# pcb.net
KiCad netlist of a schematic drawn in EAGLE
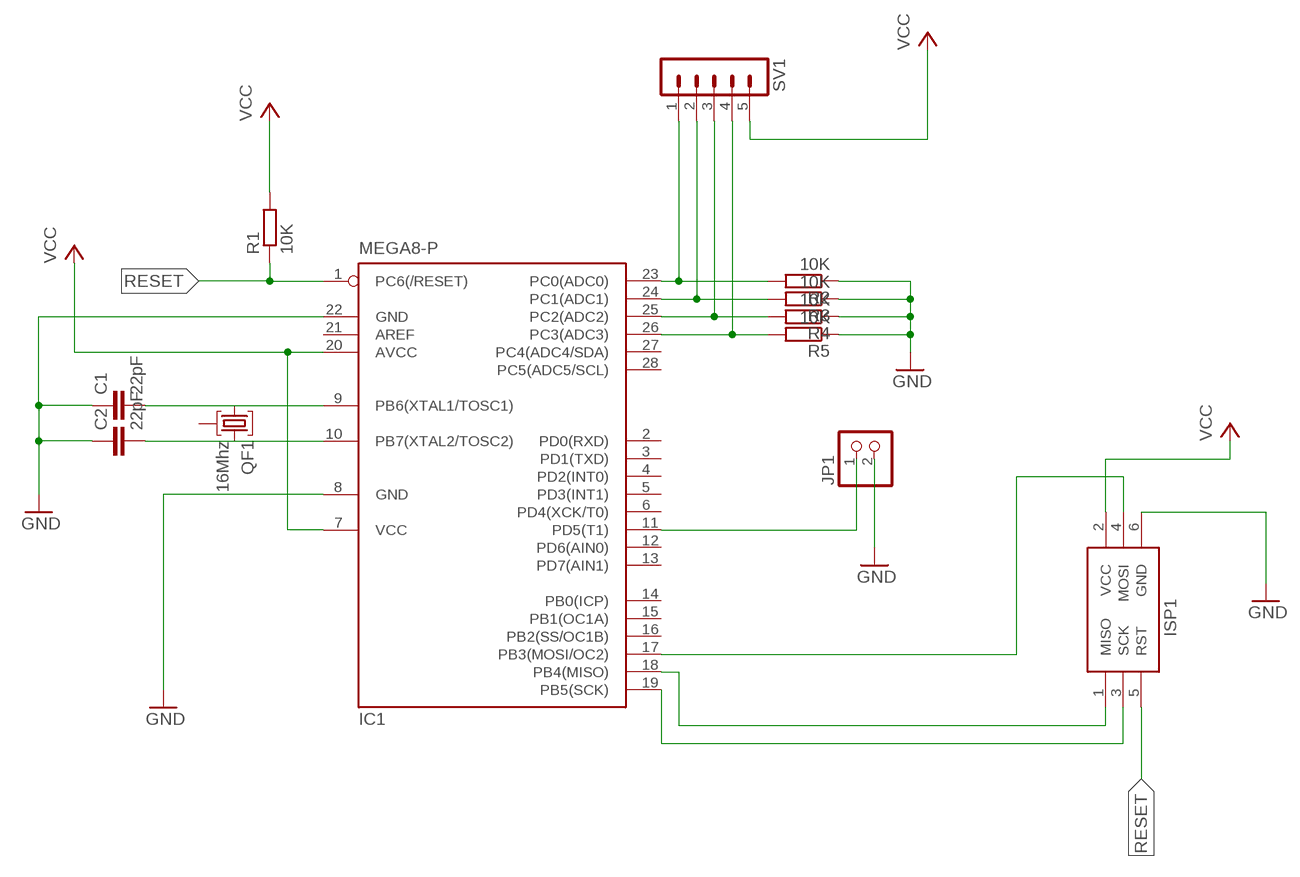
[diagram p0: schematic, sheet 1]

(export (version "E")
  (design (tool "Eeschema 10.0.6"))
  (components
    (comp (ref "C1")
      (value "22pF")
      (footprint "eagle-import:C025-025X050")
      (libsource (lib "eagle-import") (part "C-EU025-025X050"))
    )
    (comp (ref "C2")
      (value "22pF")
      (footprint "eagle-import:C025-025X050")
      (libsource (lib "eagle-import") (part "C-EU025-025X050"))
    )
    (comp (ref "IC1")
      (value "MEGA8-P")
      (footprint "eagle-import:DIL28-3")
      (libsource (lib "eagle-import") (part "MEGA8-P"))
    )
    (comp (ref "ISP1")
      (value "AVRISP-6")
      (footprint "eagle-import:AVRISP")
      (libsource (lib "eagle-import") (part "AVRISP-6"))
    )
    (comp (ref "JP1")
      (value "PINHD-1X2")
      (footprint "eagle-import:1X02")
      (libsource (lib "eagle-import") (part "PINHD-1X2"))
    )
    (comp (ref "QF1")
      (value "16Mhz")
      (footprint "eagle-import:HC49U")
      (libsource (lib "eagle-import") (part "8M10AHC49T"))
    )
    (comp (ref "R1")
      (value "10K")
      (footprint "eagle-import:0204_5")
      (libsource (lib "eagle-import") (part "R-EU_0204/5"))
    )
    (comp (ref "R2")
      (value "10K")
      (footprint "eagle-import:0204_5")
      (libsource (lib "eagle-import") (part "R-EU_0204/5"))
    )
    (comp (ref "R3")
      (value "10K")
      (footprint "eagle-import:0204_5")
      (libsource (lib "eagle-import") (part "R-EU_0204/5"))
    )
    (comp (ref "R4")
      (value "10K")
      (footprint "eagle-import:0204_5")
      (libsource (lib "eagle-import") (part "R-EU_0204/5"))
    )
    (comp (ref "R5")
      (value "10K")
      (footprint "eagle-import:0204_5")
      (libsource (lib "eagle-import") (part "R-EU_0204/5"))
    )
    (comp (ref "SV1")
      (value "MA05-1")
      (footprint "eagle-import:MA05-1")
      (libsource (lib "eagle-import") (part "MA05-1"))
    )
  )
  (nets
    (net (code "1") (name "GND") (class "Default")
      (node (ref "C1") (pin "1") (pinfunction "1_1") (pintype "passive"))
      (node (ref "C2") (pin "1") (pinfunction "1_1") (pintype "passive"))
      (node (ref "IC1") (pin "22") (pinfunction "GND_22") (pintype "power_in"))
      (node (ref "IC1") (pin "8") (pinfunction "GND_8") (pintype "power_in"))
      (node (ref "ISP1") (pin "6") (pinfunction "GND_6") (pintype "power_in"))
      (node (ref "JP1") (pin "2") (pinfunction "2_2") (pintype "passive"))
      (node (ref "R2") (pin "1") (pinfunction "1_1") (pintype "passive"))
      (node (ref "R3") (pin "1") (pinfunction "1_1") (pintype "passive"))
      (node (ref "R4") (pin "1") (pinfunction "1_1") (pintype "passive"))
      (node (ref "R5") (pin "1") (pinfunction "1_1") (pintype "passive"))
    )
    (net (code "2") (name "Net-(IC1-PB3(MOSI{slash}OC2))") (class "Default")
      (node (ref "IC1") (pin "17") (pinfunction "PB3(MOSI/OC2)_17") (pintype "bidirectional"))
      (node (ref "ISP1") (pin "4") (pinfunction "MOSI_4") (pintype "output"))
    )
    (net (code "3") (name "Net-(IC1-PB4(MISO))") (class "Default")
      (node (ref "IC1") (pin "18") (pinfunction "PB4(MISO)_18") (pintype "bidirectional"))
      (node (ref "ISP1") (pin "1") (pinfunction "MISO_1") (pintype "input"))
    )
    (net (code "4") (name "Net-(IC1-PB5(SCK))") (class "Default")
      (node (ref "IC1") (pin "19") (pinfunction "PB5(SCK)_19") (pintype "bidirectional"))
      (node (ref "ISP1") (pin "3") (pinfunction "SCK_3") (pintype "output"))
    )
    (net (code "5") (name "Net-(IC1-PB6(XTAL1{slash}TOSC1))") (class "Default")
      (node (ref "C1") (pin "2") (pinfunction "2_2") (pintype "passive"))
      (node (ref "IC1") (pin "9") (pinfunction "PB6(XTAL1/TOSC1)_9") (pintype "bidirectional"))
      (node (ref "QF1") (pin "1") (pinfunction "1_1") (pintype "passive"))
    )
    (net (code "6") (name "Net-(IC1-PB7(XTAL2{slash}TOSC2))") (class "Default")
      (node (ref "C2") (pin "2") (pinfunction "2_2") (pintype "passive"))
      (node (ref "IC1") (pin "10") (pinfunction "PB7(XTAL2/TOSC2)_10") (pintype "bidirectional"))
      (node (ref "QF1") (pin "3") (pinfunction "3_3") (pintype "passive"))
    )
    (net (code "7") (name "Net-(IC1-PC0(ADC0))") (class "Default")
      (node (ref "IC1") (pin "23") (pinfunction "PC0(ADC0)_23") (pintype "bidirectional"))
      (node (ref "R2") (pin "2") (pinfunction "2_2") (pintype "passive"))
      (node (ref "SV1") (pin "1") (pinfunction "1_1") (pintype "passive"))
    )
    (net (code "8") (name "Net-(IC1-PC1(ADC1))") (class "Default")
      (node (ref "IC1") (pin "24") (pinfunction "PC1(ADC1)_24") (pintype "bidirectional"))
      (node (ref "R3") (pin "2") (pinfunction "2_2") (pintype "passive"))
      (node (ref "SV1") (pin "2") (pinfunction "2_2") (pintype "passive"))
    )
    (net (code "9") (name "Net-(IC1-PC2(ADC2))") (class "Default")
      (node (ref "IC1") (pin "25") (pinfunction "PC2(ADC2)_25") (pintype "bidirectional"))
      (node (ref "R4") (pin "2") (pinfunction "2_2") (pintype "passive"))
      (node (ref "SV1") (pin "3") (pinfunction "3_3") (pintype "passive"))
    )
    (net (code "10") (name "Net-(IC1-PC3(ADC3))") (class "Default")
      (node (ref "IC1") (pin "26") (pinfunction "PC3(ADC3)_26") (pintype "bidirectional"))
      (node (ref "R5") (pin "2") (pinfunction "2_2") (pintype "passive"))
      (node (ref "SV1") (pin "4") (pinfunction "4_4") (pintype "passive"))
    )
    (net (code "11") (name "Net-(IC1-PD5(T1))") (class "Default")
      (node (ref "IC1") (pin "11") (pinfunction "PD5(T1)_11") (pintype "bidirectional"))
      (node (ref "JP1") (pin "1") (pinfunction "1_1") (pintype "passive"))
    )
    (net (code "12") (name "RESET") (class "Default")
      (node (ref "IC1") (pin "1") (pinfunction "PC6(/RESET)_1") (pintype "bidirectional"))
      (node (ref "ISP1") (pin "5") (pinfunction "RST_5") (pintype "output"))
      (node (ref "R1") (pin "1") (pinfunction "1_1") (pintype "passive"))
    )
    (net (code "13") (name "VCC") (class "Default")
      (node (ref "IC1") (pin "20") (pinfunction "AVCC_20") (pintype "power_in"))
      (node (ref "IC1") (pin "7") (pinfunction "VCC_7") (pintype "power_in"))
      (node (ref "ISP1") (pin "2") (pinfunction "VCC_2") (pintype "power_in"))
      (node (ref "R1") (pin "2") (pinfunction "2_2") (pintype "passive"))
      (node (ref "SV1") (pin "5") (pinfunction "5_5") (pintype "passive"))
    )
    (net (code "14") (name "unconnected-(IC1-AREF-Pad21)") (class "Default")
      (node (ref "IC1") (pin "21") (pinfunction "AREF_21") (pintype "passive"))
    )
    (net (code "15") (name "unconnected-(IC1-PB0(ICP)-Pad14)") (class "Default")
      (node (ref "IC1") (pin "14") (pinfunction "PB0(ICP)_14") (pintype "bidirectional"))
    )
    (net (code "16") (name "unconnected-(IC1-PB1(OC1A)-Pad15)") (class "Default")
      (node (ref "IC1") (pin "15") (pinfunction "PB1(OC1A)_15") (pintype "bidirectional"))
    )
    (net (code "17") (name "unconnected-(IC1-PB2(SS{slash}OC1B)-Pad16)") (class "Default")
      (node (ref "IC1") (pin "16") (pinfunction "PB2(SS/OC1B)_16") (pintype "bidirectional"))
    )
    (net (code "18") (name "unconnected-(IC1-PC4(ADC4{slash}SDA)-Pad27)") (class "Default")
      (node (ref "IC1") (pin "27") (pinfunction "PC4(ADC4/SDA)_27") (pintype "bidirectional"))
    )
    (net (code "19") (name "unconnected-(IC1-PC5(ADC5{slash}SCL)-Pad28)") (class "Default")
      (node (ref "IC1") (pin "28") (pinfunction "PC5(ADC5/SCL)_28") (pintype "bidirectional"))
    )
    (net (code "20") (name "unconnected-(IC1-PD0(RXD)-Pad2)") (class "Default")
      (node (ref "IC1") (pin "2") (pinfunction "PD0(RXD)_2") (pintype "bidirectional"))
    )
    (net (code "21") (name "unconnected-(IC1-PD1(TXD)-Pad3)") (class "Default")
      (node (ref "IC1") (pin "3") (pinfunction "PD1(TXD)_3") (pintype "bidirectional"))
    )
    (net (code "22") (name "unconnected-(IC1-PD2(INT0)-Pad4)") (class "Default")
      (node (ref "IC1") (pin "4") (pinfunction "PD2(INT0)_4") (pintype "bidirectional"))
    )
    (net (code "23") (name "unconnected-(IC1-PD3(INT1)-Pad5)") (class "Default")
      (node (ref "IC1") (pin "5") (pinfunction "PD3(INT1)_5") (pintype "bidirectional"))
    )
    (net (code "24") (name "unconnected-(IC1-PD4(XCK{slash}T0)-Pad6)") (class "Default")
      (node (ref "IC1") (pin "6") (pinfunction "PD4(XCK/T0)_6") (pintype "bidirectional"))
    )
    (net (code "25") (name "unconnected-(IC1-PD6(AIN0)-Pad12)") (class "Default")
      (node (ref "IC1") (pin "12") (pinfunction "PD6(AIN0)_12") (pintype "bidirectional"))
    )
    (net (code "26") (name "unconnected-(IC1-PD7(AIN1)-Pad13)") (class "Default")
      (node (ref "IC1") (pin "13") (pinfunction "PD7(AIN1)_13") (pintype "bidirectional"))
    )
    (net (code "27") (name "unconnected-(QF1-Pad2)") (class "Default")
      (node (ref "QF1") (pin "2") (pinfunction "2_2") (pintype "passive"))
    )
  )
)
